# microsd.net
KiCad netlist of a schematic drawn in Altium Designer
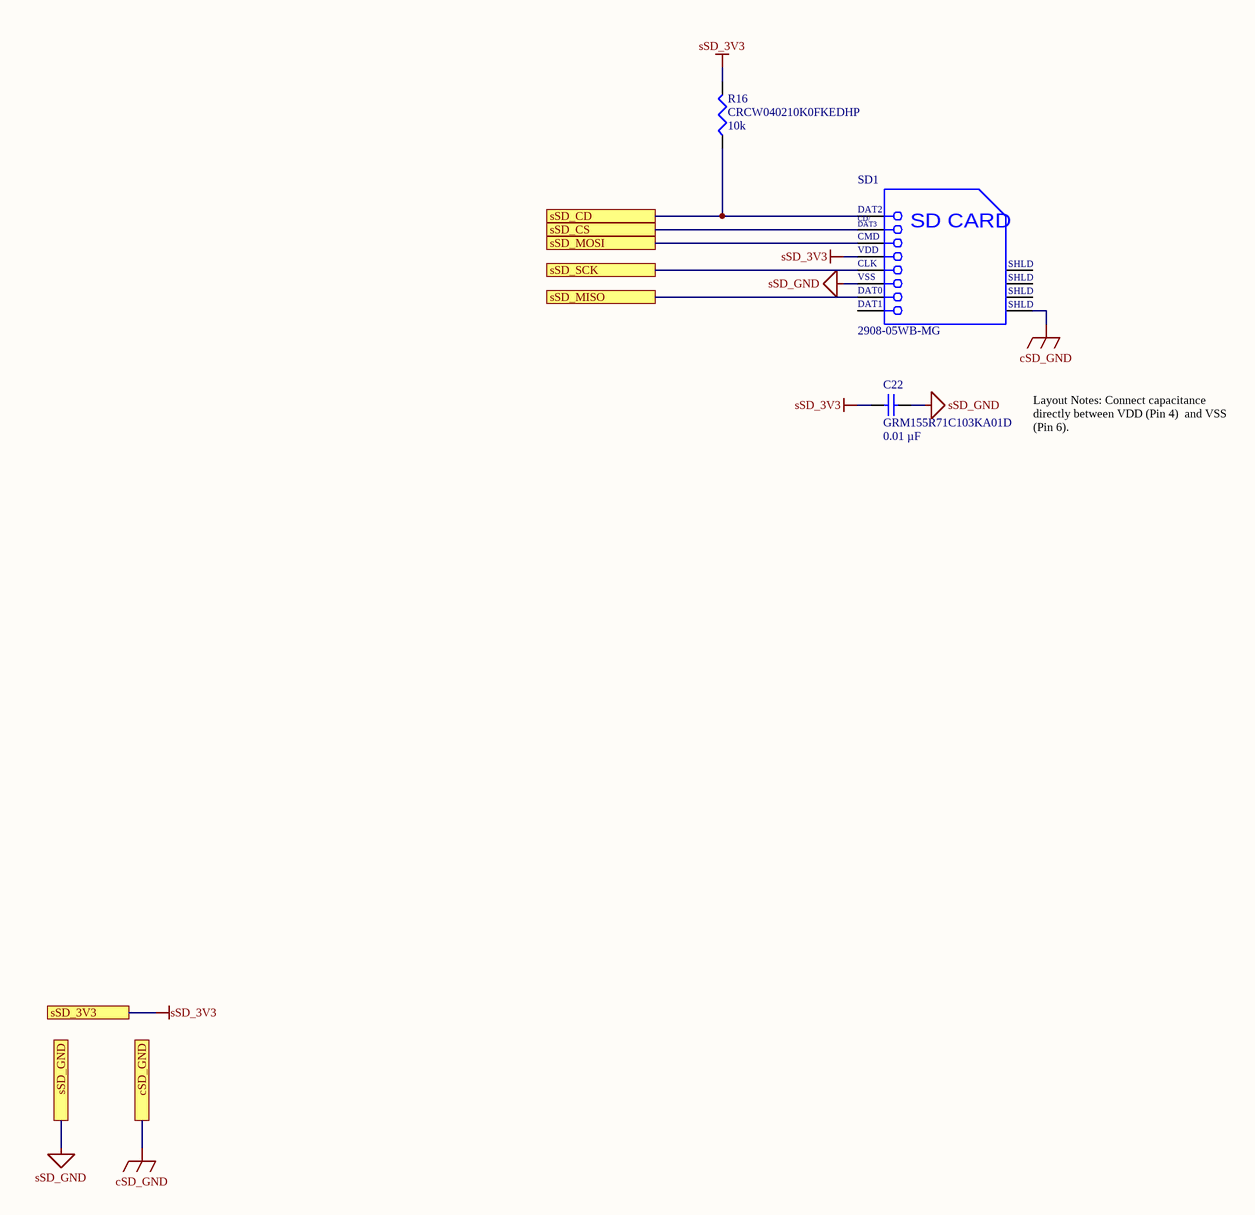
[diagram p0: _microsd.SchDoc]

(export (version "E")
  (design (tool "Eeschema 10.0.6"))
  (components
    (comp (ref "C22")
      (value "GRM155R71C103KA01D")
      (footprint "0402")
      (description "Cap, 0.01 µF, 16 V, X7R")
      (fields (field (name "ALTIUM_VALUE") "0.01 µF") (field (name "PUBLISHER") "Altium Limited"))
      (libsource (lib "miscellaneous_devices") (part "Cap"))
    )
    (comp (ref "R16")
      (value "CRCW040210K0FKEDHP")
      (footprint "0402")
      (description "0.125W, -55-155C, 1005, 50V, ±1%")
      (fields (field (name "ALTIUM_VALUE") "10k"))
      (libsource (lib "standard_resistors") (part "CRCW0402xxxxFKED"))
    )
    (comp (ref "SD1")
      (value "2908-05WB-MG")
      (footprint "3M-2908-05WB-MG_V")
      (description "Card Connector Micro-SD, 500 VAC, 100 mOhm Min, 0.5 A, RoHS, Tape and Reel")
      (fields (field (name "MANUFACTURER") "3M"))
      (libsource (lib "Altium Content Vault") (part "CN-SD-8-4S"))
    )
  )
  (nets
    (net (code "1") (name "/sSD_CD") (class "Default")
      (node (ref "R16") (pin "1") (pinfunction "1_1") (pintype "passive"))
      (node (ref "SD1") (pin "1") (pinfunction "DAT2_1") (pintype "passive"))
    )
    (net (code "2") (name "/sSD_CS") (class "Default")
      (node (ref "SD1") (pin "2") (pinfunction "CD/DAT3_2") (pintype "passive"))
    )
    (net (code "3") (name "/sSD_MISO") (class "Default")
      (node (ref "SD1") (pin "7") (pinfunction "DAT0_7") (pintype "passive"))
    )
    (net (code "4") (name "/sSD_MOSI") (class "Default")
      (node (ref "SD1") (pin "3") (pinfunction "CMD_3") (pintype "passive"))
    )
    (net (code "5") (name "/sSD_SCK") (class "Default")
      (node (ref "SD1") (pin "5") (pinfunction "CLK_5") (pintype "passive"))
    )
    (net (code "6") (name "cSD_GND") (class "Default")
      (node (ref "SD1") (pin "12") (pinfunction "SHLD_12") (pintype "passive"))
    )
    (net (code "7") (name "sSD_3V3") (class "Default")
      (node (ref "C22") (pin "2") (pinfunction "2_2") (pintype "passive"))
      (node (ref "R16") (pin "2") (pinfunction "2_2") (pintype "passive"))
      (node (ref "SD1") (pin "4") (pinfunction "VDD_4") (pintype "passive"))
    )
    (net (code "8") (name "sSD_GND") (class "Default")
      (node (ref "C22") (pin "1") (pinfunction "1_1") (pintype "passive"))
      (node (ref "SD1") (pin "6") (pinfunction "VSS_6") (pintype "passive"))
    )
    (net (code "9") (name "unconnected-(SD1-DAT1-Pad8)") (class "Default")
      (node (ref "SD1") (pin "8") (pinfunction "DAT1_8") (pintype "passive"))
    )
    (net (code "10") (name "unconnected-(SD1-SHLD-Pad9)") (class "Default")
      (node (ref "SD1") (pin "9") (pinfunction "SHLD_9") (pintype "passive"))
    )
    (net (code "11") (name "unconnected-(SD1-SHLD-Pad10)") (class "Default")
      (node (ref "SD1") (pin "10") (pinfunction "SHLD_10") (pintype "passive"))
    )
    (net (code "12") (name "unconnected-(SD1-SHLD-Pad11)") (class "Default")
      (node (ref "SD1") (pin "11") (pinfunction "SHLD_11") (pintype "passive"))
    )
  )
)
